# EVB-NORA-B2_SCHEM_0003_USBhub_FTDI.net
KiCad netlist of a schematic drawn in Altium Designer
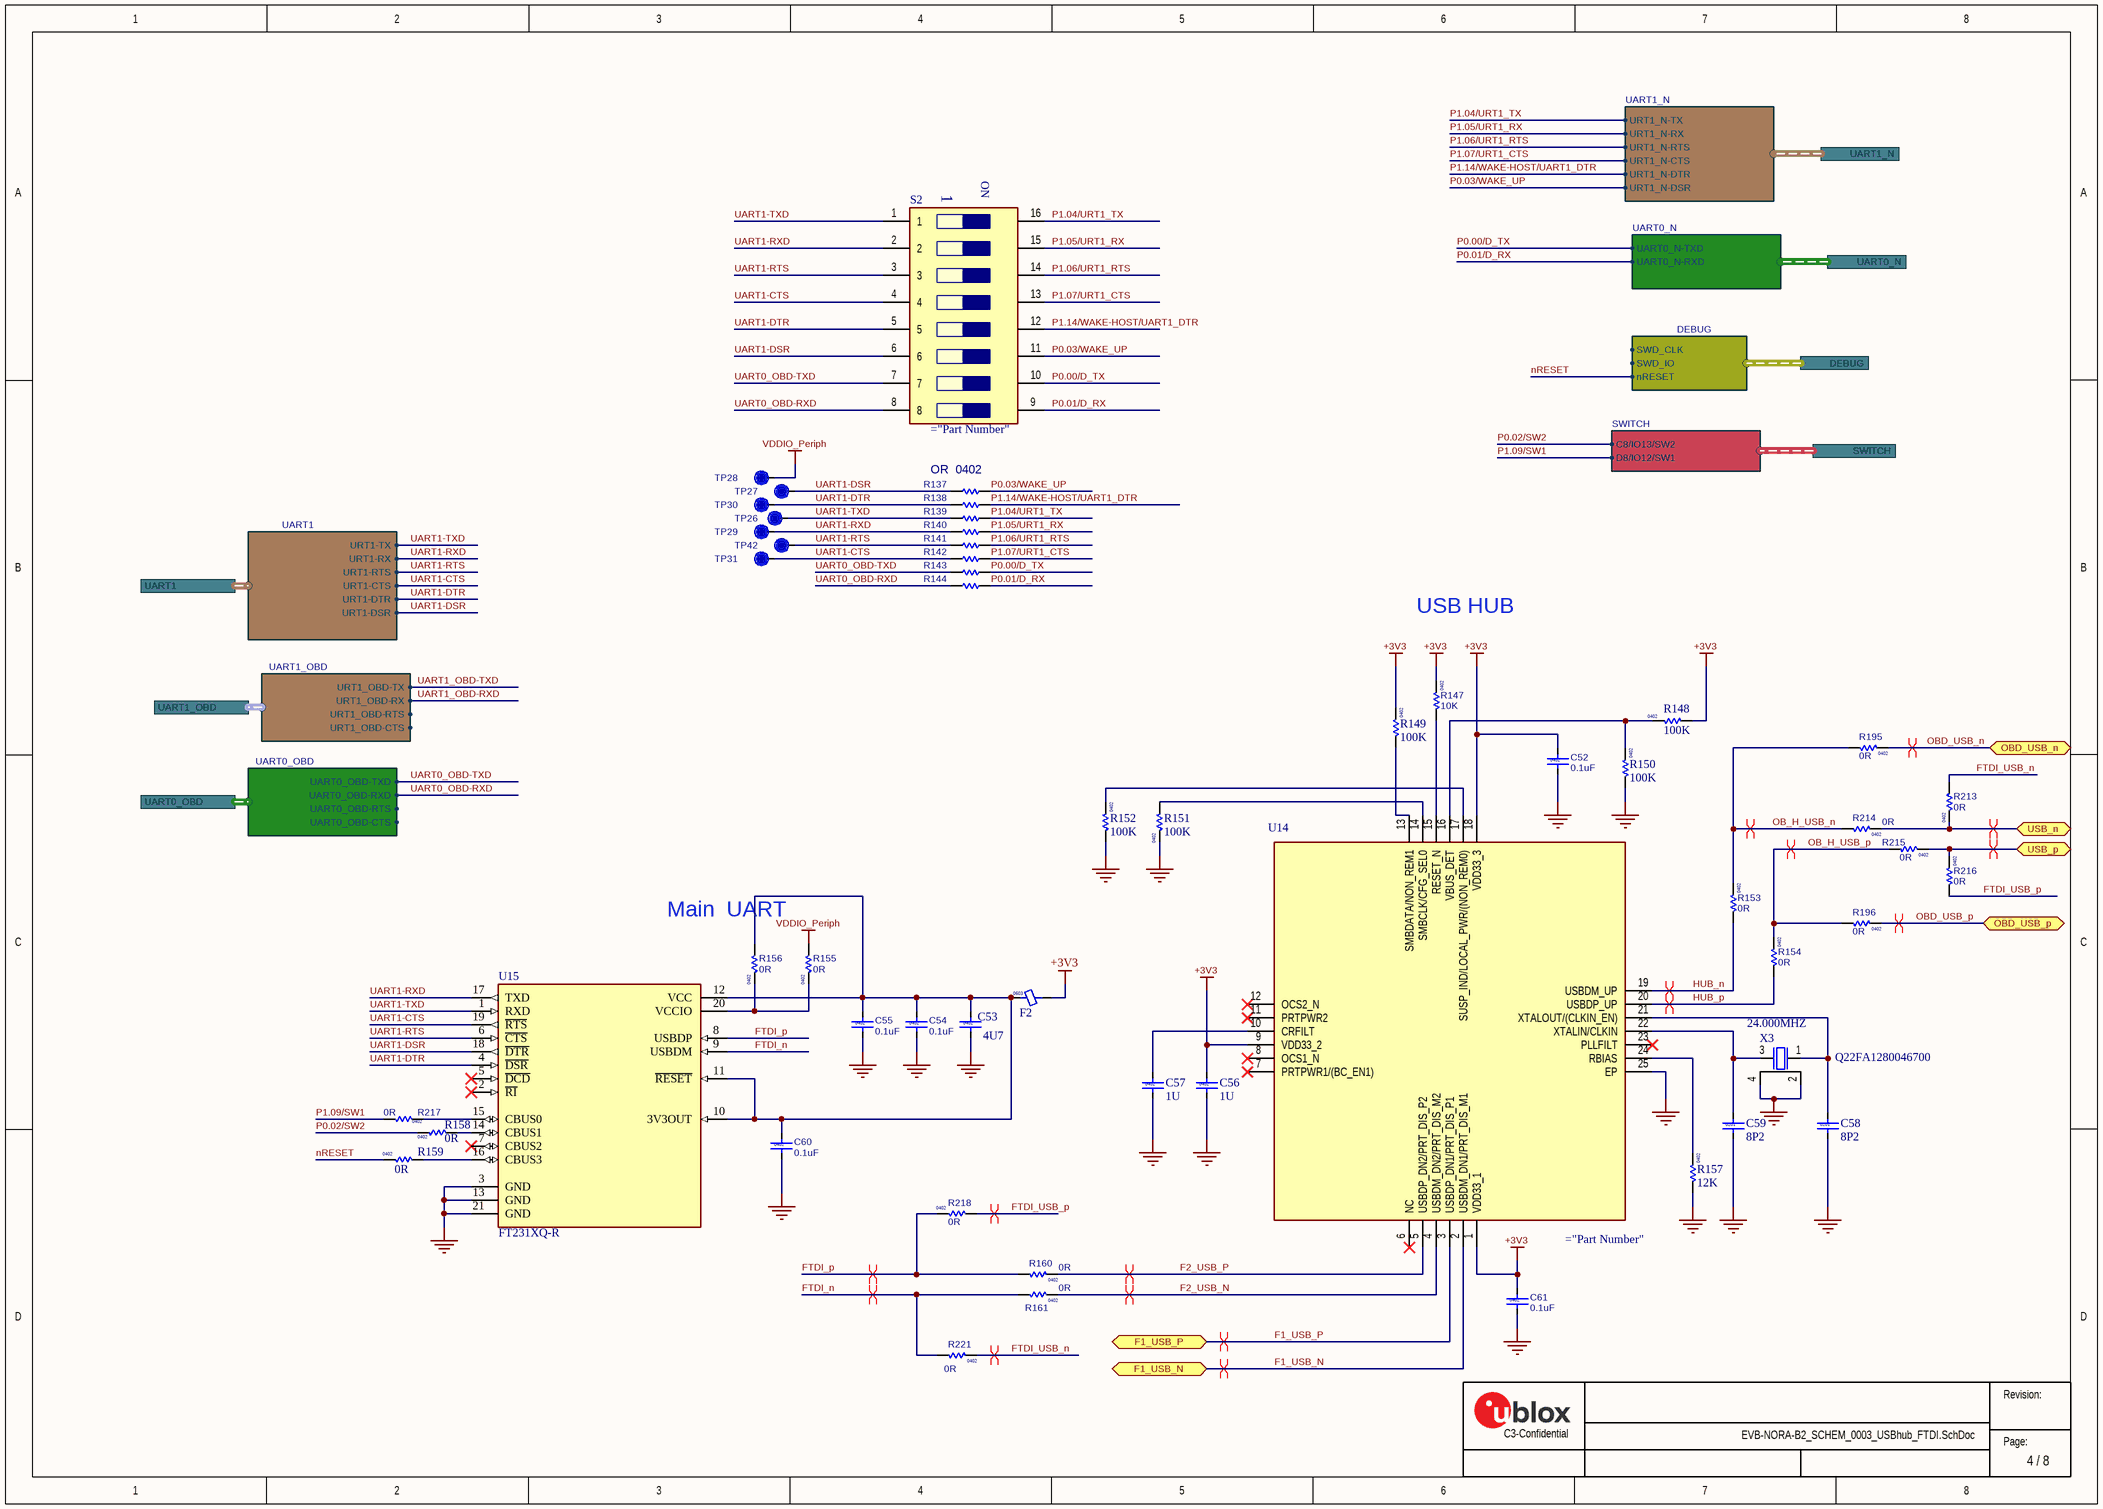
[diagram p0: EVB-NORA-B2_SCHEM_0003_USBhub_FTDI.SchDoc]

(export (version "E")
  (design (tool "Eeschema 10.0.6"))
  (components
    (comp (ref "C52")
      (value "0.1uF")
      (footprint "Cap 0402 HD")
      (description "Cap, Ceramic 0.1uF 10V 10% X5R 0402")
      (fields
        (field (name "SIZE") "0402")
        (field (name "PART NUMBER") "120-00016")
        (field (name "MANUFACTURER") "Murata Electronics North America")
      )
      (libsource (lib "Arena_Parts_DB_Lib") (part "Cap Chip"))
    )
    (comp (ref "C53")
      (value "4U7")
      (footprint "Cap 0402 HD")
      (description "CAP CER X5R 0402 4U7 20% 10V")
      (fields
        (field (name "SIZE") "0402")
        (field (name "PART NUMBER") "UBXH01-0000243")
        (field (name "TOLERANCE") "20%")
        (field (name "EDITOR") "martin.pilik")
        (field (name "RELEASED BY") "fabrice.bret-dibat")
      )
      (libsource (lib "UBX_Parts_DB_Lib") (part "Cap Chip"))
    )
    (comp (ref "C54")
      (value "0.1uF")
      (footprint "Cap 0402 HD")
      (description "Cap, Ceramic 0.1uF 10V 10% X5R 0402")
      (fields
        (field (name "SIZE") "0402")
        (field (name "PART NUMBER") "120-00016")
        (field (name "MANUFACTURER") "Murata Electronics North America")
      )
      (libsource (lib "Arena_Parts_DB_Lib") (part "Cap Chip"))
    )
    (comp (ref "C55")
      (value "0.1uF")
      (footprint "Cap 0402 HD")
      (description "Cap, Ceramic 0.1uF 10V 10% X5R 0402")
      (fields
        (field (name "SIZE") "0402")
        (field (name "PART NUMBER") "120-00016")
        (field (name "MANUFACTURER") "Murata Electronics North America")
      )
      (libsource (lib "Arena_Parts_DB_Lib") (part "Cap Chip"))
    )
    (comp (ref "C56")
      (value "1U")
      (footprint "Cap 0402 HD")
      (description "CAP CER X5R 0402 1U 10% 10V")
      (fields
        (field (name "SIZE") "0402")
        (field (name "PART NUMBER") "UBXH01-0000248")
        (field (name "TOLERANCE") "10%")
        (field (name "EDITOR") "michael.hein")
        (field (name "RELEASED BY") "igor.shevchenko")
      )
      (libsource (lib "UBX_Parts_DB_Lib") (part "Cap Chip"))
    )
    (comp (ref "C57")
      (value "1U")
      (footprint "Cap 0402 HD")
      (description "CAP CER X5R 0402 1U 10% 10V")
      (fields
        (field (name "SIZE") "0402")
        (field (name "PART NUMBER") "UBXH01-0000248")
        (field (name "TOLERANCE") "10%")
        (field (name "EDITOR") "michael.hein")
        (field (name "RELEASED BY") "igor.shevchenko")
      )
      (libsource (lib "UBX_Parts_DB_Lib") (part "Cap Chip"))
    )
    (comp (ref "C58")
      (value "8P2")
      (footprint "Cap 0201 HD")
      (description "CAP CER C0G 0201 8P2 +/-0.5P 25V")
      (fields
        (field (name "SIZE") "0201")
        (field (name "PART NUMBER") "UBXH01-0013002")
        (field (name "TOLERANCE") "+/-0.5P")
        (field (name "EDITOR") "roland.rust")
        (field (name "RELEASED BY") "roland.rust")
      )
      (libsource (lib "UBX_Parts_DB_Lib") (part "Cap Chip"))
    )
    (comp (ref "C59")
      (value "8P2")
      (footprint "Cap 0201 HD")
      (description "CAP CER C0G 0201 8P2 +/-0.5P 25V")
      (fields
        (field (name "SIZE") "0201")
        (field (name "PART NUMBER") "UBXH01-0013002")
        (field (name "TOLERANCE") "+/-0.5P")
        (field (name "EDITOR") "roland.rust")
        (field (name "RELEASED BY") "roland.rust")
      )
      (libsource (lib "UBX_Parts_DB_Lib") (part "Cap Chip"))
    )
    (comp (ref "C60")
      (value "0.1uF")
      (footprint "Cap 0402 HD")
      (description "Cap, Ceramic 0.1uF 10V 10% X5R 0402")
      (fields
        (field (name "SIZE") "0402")
        (field (name "PART NUMBER") "120-00016")
        (field (name "MANUFACTURER") "Murata Electronics North America")
      )
      (libsource (lib "Arena_Parts_DB_Lib") (part "Cap Chip"))
    )
    (comp (ref "C61")
      (value "0.1uF")
      (footprint "Cap 0402 HD")
      (description "Cap, Ceramic 0.1uF 10V 10% X5R 0402")
      (fields
        (field (name "SIZE") "0402")
        (field (name "PART NUMBER") "120-00016")
        (field (name "MANUFACTURER") "Murata Electronics North America")
      )
      (libsource (lib "Arena_Parts_DB_Lib") (part "Cap Chip"))
    )
    (comp (ref "F2")
      (value "UBXH08-0000001")
      (footprint "IND_0603_1750Lx950Wx1050H_600x800Pad_800G_FLX")
      (description "FERRITE BEAD 0603 600 OHM AT 100MHZ 600OHM 500mA")
      (fields
        (field (name "SIZE") "0603")
        (field (name "MANUFACTURER") "TDK Corporation")
        (field (name "EDITOR") "daniel.hurni")
        (field (name "RELEASED BY") "martin.frauchiger")
      )
      (libsource (lib "UBX_Parts_DB_Lib") (part "FB sm"))
    )
    (comp (ref "R137")
      (value "UBXH18-0003002")
      (footprint "RES 0402 HD")
      (description "RES THICK FILM CHIP 0402 0R 0 100mW")
      (fields
        (field (name "TOLERANCE") "0")
        (field (name "MANUFACTURER") "KOA")
        (field (name "EDITOR") "charlotte.biber")
        (field (name "RELEASED BY") "peter.mueller")
      )
      (libsource (lib "UBX_Parts_DB_Lib") (part "Res sm"))
    )
    (comp (ref "R138")
      (value "UBXH18-0003002")
      (footprint "RES 0402 HD")
      (description "RES THICK FILM CHIP 0402 0R 0 100mW")
      (fields
        (field (name "TOLERANCE") "0")
        (field (name "MANUFACTURER") "KOA")
        (field (name "EDITOR") "charlotte.biber")
        (field (name "RELEASED BY") "peter.mueller")
      )
      (libsource (lib "UBX_Parts_DB_Lib") (part "Res sm"))
    )
    (comp (ref "R139")
      (value "UBXH18-0003002")
      (footprint "RES 0402 HD")
      (description "RES THICK FILM CHIP 0402 0R 0 100mW")
      (fields
        (field (name "TOLERANCE") "0")
        (field (name "MANUFACTURER") "KOA")
        (field (name "EDITOR") "charlotte.biber")
        (field (name "RELEASED BY") "peter.mueller")
      )
      (libsource (lib "UBX_Parts_DB_Lib") (part "Res sm"))
    )
    (comp (ref "R140")
      (value "UBXH18-0003002")
      (footprint "RES 0402 HD")
      (description "RES THICK FILM CHIP 0402 0R 0 100mW")
      (fields
        (field (name "TOLERANCE") "0")
        (field (name "MANUFACTURER") "KOA")
        (field (name "EDITOR") "charlotte.biber")
        (field (name "RELEASED BY") "peter.mueller")
      )
      (libsource (lib "UBX_Parts_DB_Lib") (part "Res sm"))
    )
    (comp (ref "R141")
      (value "UBXH18-0003002")
      (footprint "RES 0402 HD")
      (description "RES THICK FILM CHIP 0402 0R 0 100mW")
      (fields
        (field (name "TOLERANCE") "0")
        (field (name "MANUFACTURER") "KOA")
        (field (name "EDITOR") "charlotte.biber")
        (field (name "RELEASED BY") "peter.mueller")
      )
      (libsource (lib "UBX_Parts_DB_Lib") (part "Res sm"))
    )
    (comp (ref "R142")
      (value "UBXH18-0003002")
      (footprint "RES 0402 HD")
      (description "RES THICK FILM CHIP 0402 0R 0 100mW")
      (fields
        (field (name "TOLERANCE") "0")
        (field (name "MANUFACTURER") "KOA")
        (field (name "EDITOR") "charlotte.biber")
        (field (name "RELEASED BY") "peter.mueller")
      )
      (libsource (lib "UBX_Parts_DB_Lib") (part "Res sm"))
    )
    (comp (ref "R143")
      (value "UBXH18-0003002")
      (footprint "RES 0402 HD")
      (description "RES THICK FILM CHIP 0402 0R 0 100mW")
      (fields
        (field (name "TOLERANCE") "0")
        (field (name "MANUFACTURER") "KOA")
        (field (name "EDITOR") "charlotte.biber")
        (field (name "RELEASED BY") "peter.mueller")
      )
      (libsource (lib "UBX_Parts_DB_Lib") (part "Res sm"))
    )
    (comp (ref "R144")
      (value "UBXH18-0003002")
      (footprint "RES 0402 HD")
      (description "RES THICK FILM CHIP 0402 0R 0 100mW")
      (fields
        (field (name "TOLERANCE") "0")
        (field (name "MANUFACTURER") "KOA")
        (field (name "EDITOR") "charlotte.biber")
        (field (name "RELEASED BY") "peter.mueller")
      )
      (libsource (lib "UBX_Parts_DB_Lib") (part "Res sm"))
    )
    (comp (ref "R147")
      (value "10K")
      (footprint "RES 0402 HD")
      (description "RES THICK FILM CHIP 0402 10K 1% 63mW")
      (fields
        (field (name "SIZE") "0402")
        (field (name "PART NUMBER") "UBXH18-0000065")
        (field (name "TOLERANCE") "1%")
        (field (name "EDITOR") "erian.bezhani")
        (field (name "RELEASED BY") "massimo.vlacci")
      )
      (libsource (lib "UBX_Parts_DB_Lib") (part "Res sm"))
    )
    (comp (ref "R148")
      (value "100K")
      (footprint "RES 0402 HD")
      (description "RES THICK FILM CHIP 0402 100K 1% 63mW")
      (fields
        (field (name "SIZE") "0402")
        (field (name "PART NUMBER") "UBXH18-0000005")
        (field (name "TOLERANCE") "1%")
        (field (name "EDITOR") "dario.antonaz")
        (field (name "RELEASED BY") "sandro.sestan")
      )
      (libsource (lib "UBX_Parts_DB_Lib") (part "Res sm"))
    )
    (comp (ref "R149")
      (value "100K")
      (footprint "RES 0402 HD")
      (description "RES THICK FILM CHIP 0402 100K 1% 63mW")
      (fields
        (field (name "SIZE") "0402")
        (field (name "PART NUMBER") "UBXH18-0000005")
        (field (name "TOLERANCE") "1%")
        (field (name "EDITOR") "dario.antonaz")
        (field (name "RELEASED BY") "sandro.sestan")
      )
      (libsource (lib "UBX_Parts_DB_Lib") (part "Res sm"))
    )
    (comp (ref "R150")
      (value "100K")
      (footprint "RES 0402 HD")
      (description "RES THICK FILM CHIP 0402 100K 1% 63mW")
      (fields
        (field (name "SIZE") "0402")
        (field (name "PART NUMBER") "UBXH18-0000005")
        (field (name "TOLERANCE") "1%")
        (field (name "EDITOR") "dario.antonaz")
        (field (name "RELEASED BY") "sandro.sestan")
      )
      (libsource (lib "UBX_Parts_DB_Lib") (part "Res sm"))
    )
    (comp (ref "R151")
      (value "100K")
      (footprint "RES 0402 HD")
      (description "RES THICK FILM CHIP 0402 100K 1% 63mW")
      (fields
        (field (name "SIZE") "0402")
        (field (name "PART NUMBER") "UBXH18-0000005")
        (field (name "TOLERANCE") "1%")
        (field (name "EDITOR") "dario.antonaz")
        (field (name "RELEASED BY") "sandro.sestan")
      )
      (libsource (lib "UBX_Parts_DB_Lib") (part "Res sm"))
    )
    (comp (ref "R152")
      (value "100K")
      (footprint "RES 0402 HD")
      (description "RES THICK FILM CHIP 0402 100K 1% 63mW")
      (fields
        (field (name "SIZE") "0402")
        (field (name "PART NUMBER") "UBXH18-0000005")
        (field (name "TOLERANCE") "1%")
        (field (name "EDITOR") "dario.antonaz")
        (field (name "RELEASED BY") "sandro.sestan")
      )
      (libsource (lib "UBX_Parts_DB_Lib") (part "Res sm"))
    )
    (comp (ref "R153")
      (value "0R")
      (footprint "RES 0402 HD")
      (description "RES THICK FILM CHIP 0402 0R 0 100mW")
      (fields
        (field (name "SIZE") "0402")
        (field (name "PART NUMBER") "UBXH18-0003002")
        (field (name "TOLERANCE") "0")
        (field (name "EDITOR") "charlotte.biber")
        (field (name "RELEASED BY") "peter.mueller")
      )
      (libsource (lib "UBX_Parts_DB_Lib") (part "Res sm"))
    )
    (comp (ref "R154")
      (value "0R")
      (footprint "RES 0402 HD")
      (description "RES THICK FILM CHIP 0402 0R 0 100mW")
      (fields
        (field (name "SIZE") "0402")
        (field (name "PART NUMBER") "UBXH18-0003002")
        (field (name "TOLERANCE") "0")
        (field (name "EDITOR") "charlotte.biber")
        (field (name "RELEASED BY") "peter.mueller")
      )
      (libsource (lib "UBX_Parts_DB_Lib") (part "Res sm"))
    )
    (comp (ref "R155")
      (value "0R")
      (footprint "RES 0402 HD")
      (description "RES THICK FILM CHIP 0402 0R 0 100mW")
      (fields
        (field (name "SIZE") "0402")
        (field (name "PART NUMBER") "UBXH18-0003002")
        (field (name "TOLERANCE") "0")
        (field (name "EDITOR") "charlotte.biber")
        (field (name "RELEASED BY") "peter.mueller")
      )
      (libsource (lib "UBX_Parts_DB_Lib") (part "Res sm"))
    )
    (comp (ref "R156")
      (value "0R")
      (footprint "RES 0402 HD")
      (description "RES THICK FILM CHIP 0402 0R 0 100mW")
      (fields
        (field (name "SIZE") "0402")
        (field (name "PART NUMBER") "UBXH18-0003002")
        (field (name "TOLERANCE") "0")
        (field (name "EDITOR") "charlotte.biber")
        (field (name "RELEASED BY") "peter.mueller")
      )
      (libsource (lib "UBX_Parts_DB_Lib") (part "Res sm"))
    )
    (comp (ref "R157")
      (value "12K")
      (footprint "RES_0402_1100Lx600Wx400H_500x600Pad_400G_FLX")
      (description "RES THICK FILM CHIP 0402 12K 1% 62.5mW")
      (fields
        (field (name "SIZE") "0402")
        (field (name "PART NUMBER") "UBXH18-0000133")
        (field (name "TOLERANCE") "1%")
        (field (name "EDITOR") "pierpaolo.arban")
        (field (name "RELEASED BY") "dario.antonaz")
      )
      (libsource (lib "UBX_Parts_DB_Lib") (part "Res sm"))
    )
    (comp (ref "R158")
      (value "0R")
      (footprint "RES_0402_1100Lx600Wx400H_500x600Pad_400G_FLX")
      (description "RES THICK FILM CHIP 0402 0R 0 100mW")
      (fields
        (field (name "SIZE") "0402")
        (field (name "PART NUMBER") "UBXH18-0003002")
        (field (name "TOLERANCE") "0")
        (field (name "EDITOR") "charlotte.biber")
        (field (name "RELEASED BY") "peter.mueller")
      )
      (libsource (lib "UBX_Parts_DB_Lib") (part "Res sm"))
    )
    (comp (ref "R159")
      (value "0R")
      (footprint "RES_0402_1100Lx600Wx400H_500x600Pad_400G_FLX")
      (description "RES THICK FILM CHIP 0402 0R 0 100mW")
      (fields
        (field (name "SIZE") "0402")
        (field (name "PART NUMBER") "UBXH18-0003002")
        (field (name "TOLERANCE") "0")
        (field (name "EDITOR") "charlotte.biber")
        (field (name "RELEASED BY") "peter.mueller")
      )
      (libsource (lib "UBX_Parts_DB_Lib") (part "Res sm"))
    )
    (comp (ref "R160")
      (value "0R")
      (footprint "RES 0402 HD")
      (description "RES THICK FILM CHIP 0402 0R 0 100mW")
      (fields
        (field (name "SIZE") "0402")
        (field (name "PART NUMBER") "UBXH18-0003002")
        (field (name "TOLERANCE") "0")
        (field (name "EDITOR") "charlotte.biber")
        (field (name "RELEASED BY") "peter.mueller")
      )
      (libsource (lib "UBX_Parts_DB_Lib") (part "Res sm"))
    )
    (comp (ref "R161")
      (value "0R")
      (footprint "RES 0402 HD")
      (description "RES THICK FILM CHIP 0402 0R 0 100mW")
      (fields
        (field (name "SIZE") "0402")
        (field (name "PART NUMBER") "UBXH18-0003002")
        (field (name "TOLERANCE") "0")
        (field (name "EDITOR") "charlotte.biber")
        (field (name "RELEASED BY") "peter.mueller")
      )
      (libsource (lib "UBX_Parts_DB_Lib") (part "Res sm"))
    )
    (comp (ref "R195")
      (value "0R")
      (footprint "RES 0402 HD")
      (description "RES THICK FILM CHIP 0402 0R 0 100mW")
      (fields
        (field (name "SIZE") "0402")
        (field (name "PART NUMBER") "UBXH18-0003002")
        (field (name "TOLERANCE") "0")
        (field (name "EDITOR") "charlotte.biber")
        (field (name "RELEASED BY") "peter.mueller")
      )
      (libsource (lib "UBX_Parts_DB_Lib") (part "Res sm"))
    )
    (comp (ref "R196")
      (value "0R")
      (footprint "RES 0402 HD")
      (description "RES THICK FILM CHIP 0402 0R 0 100mW")
      (fields
        (field (name "SIZE") "0402")
        (field (name "PART NUMBER") "UBXH18-0003002")
        (field (name "TOLERANCE") "0")
        (field (name "EDITOR") "charlotte.biber")
        (field (name "RELEASED BY") "peter.mueller")
      )
      (libsource (lib "UBX_Parts_DB_Lib") (part "Res sm"))
    )
    (comp (ref "R213")
      (value "0R")
      (footprint "RES 0402 HD")
      (description "RES THICK FILM CHIP 0402 0R 0 100mW")
      (fields
        (field (name "SIZE") "0402")
        (field (name "PART NUMBER") "UBXH18-0003002")
        (field (name "TOLERANCE") "0")
        (field (name "EDITOR") "charlotte.biber")
        (field (name "RELEASED BY") "peter.mueller")
      )
      (libsource (lib "UBX_Parts_DB_Lib") (part "Res sm"))
    )
    (comp (ref "R214")
      (value "0R")
      (footprint "RES 0402 HD")
      (description "RES THICK FILM CHIP 0402 0R 0 100mW")
      (fields
        (field (name "SIZE") "0402")
        (field (name "PART NUMBER") "UBXH18-0003002")
        (field (name "TOLERANCE") "0")
        (field (name "EDITOR") "charlotte.biber")
        (field (name "RELEASED BY") "peter.mueller")
      )
      (libsource (lib "UBX_Parts_DB_Lib") (part "Res sm"))
    )
    (comp (ref "R215")
      (value "0R")
      (footprint "RES 0402 HD")
      (description "RES THICK FILM CHIP 0402 0R 0 100mW")
      (fields
        (field (name "SIZE") "0402")
        (field (name "PART NUMBER") "UBXH18-0003002")
        (field (name "TOLERANCE") "0")
        (field (name "EDITOR") "charlotte.biber")
        (field (name "RELEASED BY") "peter.mueller")
      )
      (libsource (lib "UBX_Parts_DB_Lib") (part "Res sm"))
    )
    (comp (ref "R216")
      (value "0R")
      (footprint "RES 0402 HD")
      (description "RES THICK FILM CHIP 0402 0R 0 100mW")
      (fields
        (field (name "SIZE") "0402")
        (field (name "PART NUMBER") "UBXH18-0003002")
        (field (name "TOLERANCE") "0")
        (field (name "EDITOR") "charlotte.biber")
        (field (name "RELEASED BY") "peter.mueller")
      )
      (libsource (lib "UBX_Parts_DB_Lib") (part "Res sm"))
    )
    (comp (ref "R217")
      (value "0R")
      (footprint "RES 0402 HD")
      (description "RES THICK FILM CHIP 0402 0R 0 100mW")
      (fields
        (field (name "SIZE") "0402")
        (field (name "PART NUMBER") "UBXH18-0003002")
        (field (name "TOLERANCE") "0")
        (field (name "EDITOR") "charlotte.biber")
        (field (name "RELEASED BY") "peter.mueller")
      )
      (libsource (lib "UBX_Parts_DB_Lib") (part "Res sm"))
    )
    (comp (ref "R218")
      (value "0R")
      (footprint "RES 0402 HD")
      (description "RES THICK FILM CHIP 0402 0R 0 100mW")
      (fields
        (field (name "SIZE") "0402")
        (field (name "PART NUMBER") "UBXH18-0003002")
        (field (name "TOLERANCE") "0")
        (field (name "EDITOR") "charlotte.biber")
        (field (name "RELEASED BY") "peter.mueller")
      )
      (libsource (lib "UBX_Parts_DB_Lib") (part "Res sm"))
    )
    (comp (ref "R221")
      (value "0R")
      (footprint "RES 0402 HD")
      (description "RES THICK FILM CHIP 0402 0R 0 100mW")
      (fields
        (field (name "SIZE") "0402")
        (field (name "PART NUMBER") "UBXH18-0003002")
        (field (name "TOLERANCE") "0")
        (field (name "EDITOR") "charlotte.biber")
        (field (name "RELEASED BY") "peter.mueller")
      )
      (libsource (lib "UBX_Parts_DB_Lib") (part "Res sm"))
    )
    (comp (ref "S2")
      (value "~")
      (footprint "2188LPSTJ")
      (description "Switch")
      (fields
        (field (name "MANUFACTURER_PART_NUMBER") "218-8LPSTJ")
        (field (name "MOUSER PART NUMBER") "774-2188LPSTJ")
      )
      (libsource (lib "SamacSys") (part "218-8LPSTJ"))
    )
    (comp (ref "TP26")
      (value "TP10R")
      (footprint "TP10R")
      (description "Testpoint, Round 1.0mm Dia")
      (fields (field (name "ADDED BY") "Jeremy D") (field (name "CHECKED BY") "Paul B"))
      (libsource (lib "LEGACY_Rigado_AltiumLib") (part "TP_R"))
    )
    (comp (ref "TP27")
      (value "TP10R")
      (footprint "TP10R")
      (description "Testpoint, Round 1.0mm Dia")
      (fields (field (name "ADDED BY") "Jeremy D") (field (name "CHECKED BY") "Paul B"))
      (libsource (lib "LEGACY_Rigado_AltiumLib") (part "TP_R"))
    )
    (comp (ref "TP28")
      (value "TP10R")
      (footprint "TP10R")
      (description "Testpoint, Round 1.0mm Dia")
      (fields (field (name "ADDED BY") "Jeremy D") (field (name "CHECKED BY") "Paul B"))
      (libsource (lib "LEGACY_Rigado_AltiumLib") (part "TP_R"))
    )
    (comp (ref "TP29")
      (value "TP10R")
      (footprint "TP10R")
      (description "Testpoint, Round 1.0mm Dia")
      (fields (field (name "ADDED BY") "Jeremy D") (field (name "CHECKED BY") "Paul B"))
      (libsource (lib "LEGACY_Rigado_AltiumLib") (part "TP_R"))
    )
    (comp (ref "TP30")
      (value "TP10R")
      (footprint "TP10R")
      (description "Testpoint, Round 1.0mm Dia")
      (fields (field (name "ADDED BY") "Jeremy D") (field (name "CHECKED BY") "Paul B"))
      (libsource (lib "LEGACY_Rigado_AltiumLib") (part "TP_R"))
    )
    (comp (ref "TP31")
      (value "TP10R")
      (footprint "TP10R")
      (description "Testpoint, Round 1.0mm Dia")
      (fields (field (name "ADDED BY") "Jeremy D") (field (name "CHECKED BY") "Paul B"))
      (libsource (lib "LEGACY_Rigado_AltiumLib") (part "TP_R"))
    )
    (comp (ref "TP42")
      (value "TP10R")
      (footprint "TP10R")
      (description "Testpoint, Round 1.0mm Dia")
      (fields (field (name "ADDED BY") "Jeremy D") (field (name "CHECKED BY") "Paul B"))
      (libsource (lib "LEGACY_Rigado_AltiumLib") (part "TP_R"))
    )
    (comp (ref "U14")
      (value "~")
      (footprint "SamacSys:QFN50P400X400X100-25N-D")
      (description "Integrated Circuit")
      (fields
        (field (name "MANUFACTURER_PART_NUMBER") "USB2422-I/MJ")
        (field (name "MOUSER PART NUMBER") "579-USB2422-I/MJ")
      )
      (libsource (lib "*") (part "USB2422-I_MJ"))
    )
    (comp (ref "U15")
      (value "FT231XQ-R")
      (footprint "QFN_5x5_FT231XQ")
      (description "FTDI USB TO SERIAL FULL UART INTERFACE QFN20")
      (fields
        (field (name "PART NUMBER") "UBXH10-0000054")
        (field (name "MANUFACTURER") "FTDI Future Technology Devices International")
        (field (name "EDITOR") "adam.johansson")
      )
      (libsource (lib "UBX_Parts_DB_Lib") (part "FT231XQ-R"))
    )
    (comp (ref "X3")
      (value "24.000MHZ")
      (footprint "XTAL_2016_HD")
      (description "CRYSTAL CL=8PF EPSON 2.0X1.6MM 24.000MHZ 30PPM")
      (fields
        (field (name "PART NUMBER") "UBXH21-0000066")
        (field (name "TOLERANCE") "30PPM")
        (field (name "MANUFACTURER P/N") "Q22FA1280046700")
        (field (name "EDITOR") "adam.johansson")
        (field (name "RELEASED BY") "olof.viklund")
      )
      (libsource (lib "UBX_Parts_DB_Lib") (part "XTAL_4Pin"))
    )
  )
  (nets
    (net (code "8") (name "+3V3") (class "Default")
      (node (ref "C52") (pin "1") (pinfunction "1_1") (pintype "passive"))
      (node (ref "C56") (pin "1") (pinfunction "1_1") (pintype "passive"))
      (node (ref "C61") (pin "1") (pinfunction "1_1") (pintype "passive"))
      (node (ref "F2") (pin "1") (pinfunction "1_1") (pintype "passive"))
      (node (ref "R147") (pin "2") (pinfunction "2_2") (pintype "passive"))
      (node (ref "R148") (pin "2") (pinfunction "2_2") (pintype "passive"))
      (node (ref "R149") (pin "2") (pinfunction "2_2") (pintype "passive"))
      (node (ref "U14") (pin "1") (pinfunction "VDD33_1_1") (pintype "passive"))
      (node (ref "U14") (pin "18") (pinfunction "VDD33_3_18") (pintype "passive"))
      (node (ref "U14") (pin "9") (pinfunction "VDD33_2_9") (pintype "passive"))
    )
    (net (code "9") (name "/F1_USB_N") (class "Default")
      (node (ref "U14") (pin "2") (pinfunction "USBDM_DN1/PRT_DIS_M1_2") (pintype "passive"))
    )
    (net (code "10") (name "/F1_USB_P") (class "Default")
      (node (ref "U14") (pin "3") (pinfunction "USBDP_DN1/PRT_DIS_P1_3") (pintype "passive"))
    )
    (net (code "11") (name "/F2_USB_N") (class "Default")
      (node (ref "R161") (pin "2") (pinfunction "2_2") (pintype "passive"))
      (node (ref "U14") (pin "4") (pinfunction "USBDM_DN2/PRT_DIS_M2_4") (pintype "passive"))
    )
    (net (code "12") (name "/F2_USB_P") (class "Default")
      (node (ref "R160") (pin "2") (pinfunction "2_2") (pintype "passive"))
      (node (ref "U14") (pin "5") (pinfunction "USBDP_DN2/PRT_DIS_P2_5") (pintype "passive"))
    )
    (net (code "13") (name "/FTDI_USB_n") (class "Default")
      (node (ref "R213") (pin "1") (pinfunction "1_1") (pintype "passive"))
      (node (ref "R221") (pin "2") (pinfunction "2_2") (pintype "passive"))
    )
    (net (code "14") (name "/FTDI_USB_p") (class "Default")
      (node (ref "R216") (pin "1") (pinfunction "1_1") (pintype "passive"))
      (node (ref "R218") (pin "1") (pinfunction "1_1") (pintype "passive"))
    )
    (net (code "15") (name "/FTDI_n") (class "Default")
      (node (ref "R161") (pin "1") (pinfunction "1_1") (pintype "passive"))
      (node (ref "R221") (pin "1") (pinfunction "1_1") (pintype "passive"))
      (node (ref "U15") (pin "9") (pinfunction "USBDM_9") (pintype "input"))
    )
    (net (code "16") (name "/FTDI_p") (class "Default")
      (node (ref "R160") (pin "1") (pinfunction "1_1") (pintype "passive"))
      (node (ref "R218") (pin "2") (pinfunction "2_2") (pintype "passive"))
      (node (ref "U15") (pin "8") (pinfunction "USBDP_8") (pintype "input"))
    )
    (net (code "17") (name "/HUB_n") (class "Default")
      (node (ref "R153") (pin "1") (pinfunction "1_1") (pintype "passive"))
      (node (ref "U14") (pin "19") (pinfunction "USBDM_UP_19") (pintype "passive"))
    )
    (net (code "18") (name "/HUB_p") (class "Default")
      (node (ref "R154") (pin "1") (pinfunction "1_1") (pintype "passive"))
      (node (ref "U14") (pin "20") (pinfunction "USBDP_UP_20") (pintype "passive"))
    )
    (net (code "19") (name "/OBD_USB_n") (class "Default")
      (node (ref "R195") (pin "2") (pinfunction "2_2") (pintype "passive"))
    )
    (net (code "20") (name "/OBD_USB_p") (class "Default")
      (node (ref "R196") (pin "2") (pinfunction "2_2") (pintype "passive"))
    )
    (net (code "21") (name "/OB_H_USB_n") (class "Default")
      (node (ref "R153") (pin "2") (pinfunction "2_2") (pintype "passive"))
      (node (ref "R195") (pin "1") (pinfunction "1_1") (pintype "passive"))
      (node (ref "R214") (pin "1") (pinfunction "1_1") (pintype "passive"))
    )
    (net (code "22") (name "/OB_H_USB_p") (class "Default")
      (node (ref "R154") (pin "2") (pinfunction "2_2") (pintype "passive"))
      (node (ref "R196") (pin "1") (pinfunction "1_1") (pintype "passive"))
      (node (ref "R215") (pin "1") (pinfunction "1_1") (pintype "passive"))
    )
    (net (code "23") (name "/P0.00{slash}D_TX") (class "Default")
      (node (ref "R143") (pin "2") (pinfunction "2_2") (pintype "passive"))
      (node (ref "S2") (pin "10") (pintype "passive"))
    )
    (net (code "24") (name "/P0.01{slash}D_RX") (class "Default")
      (node (ref "R144") (pin "2") (pinfunction "2_2") (pintype "passive"))
      (node (ref "S2") (pin "9") (pintype "passive"))
    )
    (net (code "25") (name "/P0.02{slash}SW2") (class "Default")
      (node (ref "R158") (pin "2") (pinfunction "2_2") (pintype "passive"))
    )
    (net (code "26") (name "/P0.03{slash}WAKE_UP") (class "Default")
      (node (ref "R137") (pin "2") (pinfunction "2_2") (pintype "passive"))
      (node (ref "S2") (pin "11") (pintype "passive"))
    )
    (net (code "27") (name "/P1.04{slash}URT1_TX") (class "Default")
      (node (ref "R139") (pin "2") (pinfunction "2_2") (pintype "passive"))
      (node (ref "S2") (pin "16") (pintype "passive"))
    )
    (net (code "28") (name "/P1.05{slash}URT1_RX") (class "Default")
      (node (ref "R140") (pin "2") (pinfunction "2_2") (pintype "passive"))
      (node (ref "S2") (pin "15") (pintype "passive"))
    )
    (net (code "29") (name "/P1.06{slash}URT1_RTS") (class "Default")
      (node (ref "R141") (pin "2") (pinfunction "2_2") (pintype "passive"))
      (node (ref "S2") (pin "14") (pintype "passive"))
    )
    (net (code "30") (name "/P1.07{slash}URT1_CTS") (class "Default")
      (node (ref "R142") (pin "2") (pinfunction "2_2") (pintype "passive"))
      (node (ref "S2") (pin "13") (pintype "passive"))
    )
    (net (code "31") (name "/P1.09{slash}SW1") (class "Default")
      (node (ref "R217") (pin "1") (pinfunction "1_1") (pintype "passive"))
    )
    (net (code "32") (name "/P1.14{slash}WAKE-HOST{slash}UART1_DTR") (class "Default")
      (node (ref "R138") (pin "2") (pinfunction "2_2") (pintype "passive"))
      (node (ref "S2") (pin "12") (pintype "passive"))
    )
    (net (code "33") (name "/UART0_OBD-RXD") (class "Default")
      (node (ref "R144") (pin "1") (pinfunction "1_1") (pintype "passive"))
      (node (ref "S2") (pin "8") (pinfunction "8_8") (pintype "passive"))
    )
    (net (code "34") (name "/UART0_OBD-TXD") (class "Default")
      (node (ref "R143") (pin "1") (pinfunction "1_1") (pintype "passive"))
      (node (ref "S2") (pin "7") (pinfunction "7_7") (pintype "passive"))
    )
    (net (code "35") (name "/UART1-CTS") (class "Default")
      (node (ref "R142") (pin "1") (pinfunction "1_1") (pintype "passive"))
      (node (ref "S2") (pin "4") (pinfunction "4_4") (pintype "passive"))
      (node (ref "TP31") (pin "1") (pintype "passive"))
      (node (ref "U15") (pin "19") (pinfunction "~{RTS}_19") (pintype "output"))
    )
    (net (code "36") (name "/UART1-DSR") (class "Default")
      (node (ref "R137") (pin "1") (pinfunction "1_1") (pintype "passive"))
      (node (ref "S2") (pin "6") (pinfunction "6_6") (pintype "passive"))
      (node (ref "TP27") (pin "1") (pintype "passive"))
      (node (ref "U15") (pin "18") (pinfunction "~{DTR}_18") (pintype "output"))
    )
    (net (code "37") (name "/UART1-DTR") (class "Default")
      (node (ref "R138") (pin "1") (pinfunction "1_1") (pintype "passive"))
      (node (ref "S2") (pin "5") (pinfunction "5_5") (pintype "passive"))
      (node (ref "TP30") (pin "1") (pintype "passive"))
      (node (ref "U15") (pin "4") (pinfunction "~{DSR}_4") (pintype "input"))
    )
    (net (code "38") (name "/UART1-RTS") (class "Default")
      (node (ref "R141") (pin "1") (pinfunction "1_1") (pintype "passive"))
      (node (ref "S2") (pin "3") (pinfunction "3_3") (pintype "passive"))
      (node (ref "TP42") (pin "1") (pintype "passive"))
      (node (ref "U15") (pin "6") (pinfunction "~{CTS}_6") (pintype "input"))
    )
    (net (code "39") (name "/UART1-RXD") (class "Default")
      (node (ref "R140") (pin "1") (pinfunction "1_1") (pintype "passive"))
      (node (ref "S2") (pin "2") (pinfunction "2_2") (pintype "passive"))
      (node (ref "TP29") (pin "1") (pintype "passive"))
      (node (ref "U15") (pin "17") (pinfunction "TXD_17") (pintype "output"))
    )
    (net (code "40") (name "/UART1-TXD") (class "Default")
      (node (ref "R139") (pin "1") (pinfunction "1_1") (pintype "passive"))
      (node (ref "S2") (pin "1") (pinfunction "1_1") (pintype "passive"))
      (node (ref "TP26") (pin "1") (pintype "passive"))
      (node (ref "U15") (pin "1") (pinfunction "RXD_1") (pintype "input"))
    )
    (net (code "43") (name "/USB_n") (class "Default")
      (node (ref "R213") (pin "2") (pinfunction "2_2") (pintype "passive"))
      (node (ref "R214") (pin "2") (pinfunction "2_2") (pintype "passive"))
    )
    (net (code "44") (name "/USB_p") (class "Default")
      (node (ref "R215") (pin "2") (pinfunction "2_2") (pintype "passive"))
      (node (ref "R216") (pin "2") (pinfunction "2_2") (pintype "passive"))
    )
    (net (code "45") (name "/nRESET") (class "Default")
      (node (ref "R159") (pin "2") (pinfunction "2_2") (pintype "passive"))
    )
    (net (code "53") (name "GND") (class "Default")
      (node (ref "C52") (pin "2") (pinfunction "2_2") (pintype "passive"))
      (node (ref "C53") (pin "2") (pinfunction "2_2") (pintype "passive"))
      (node (ref "C54") (pin "2") (pinfunction "2_2") (pintype "passive"))
      (node (ref "C55") (pin "2") (pinfunction "2_2") (pintype "passive"))
      (node (ref "C56") (pin "2") (pinfunction "2_2") (pintype "passive"))
      (node (ref "C57") (pin "2") (pinfunction "2_2") (pintype "passive"))
      (node (ref "C58") (pin "2") (pinfunction "2_2") (pintype "passive"))
      (node (ref "C59") (pin "2") (pinfunction "2_2") (pintype "passive"))
      (node (ref "C60") (pin "2") (pinfunction "2_2") (pintype "passive"))
      (node (ref "C61") (pin "2") (pinfunction "2_2") (pintype "passive"))
      (node (ref "R150") (pin "1") (pinfunction "1_1") (pintype "passive"))
      (node (ref "R151") (pin "2") (pinfunction "2_2") (pintype "passive"))
      (node (ref "R152") (pin "1") (pinfunction "1_1") (pintype "passive"))
      (node (ref "R157") (pin "1") (pinfunction "1_1") (pintype "passive"))
      (node (ref "U14") (pin "25") (pinfunction "EP_25") (pintype "passive"))
      (node (ref "U15") (pin "13") (pinfunction "GND_13") (pintype "power_in"))
      (node (ref "U15") (pin "21") (pinfunction "GND_21") (pintype "power_in"))
      (node (ref "U15") (pin "3") (pinfunction "GND_3") (pintype "power_in"))
      (node (ref "X3") (pin "2") (pintype "passive"))
      (node (ref "X3") (pin "4") (pintype "passive"))
    )
    (net (code "54") (name "Net-(U14-CRFILT)") (class "Default")
      (node (ref "C57") (pin "1") (pinfunction "1_1") (pintype "passive"))
      (node (ref "U14") (pin "10") (pinfunction "CRFILT_10") (pintype "passive"))
    )
    (net (code "55") (name "Net-(U14-RBIAS)") (class "Default")
      (node (ref "R157") (pin "2") (pinfunction "2_2") (pintype "passive"))
      (node (ref "U14") (pin "24") (pinfunction "RBIAS_24") (pintype "passive"))
    )
    (net (code "56") (name "Net-(U14-RESET_N)") (class "Default")
      (node (ref "R147") (pin "1") (pinfunction "1_1") (pintype "passive"))
      (node (ref "U14") (pin "15") (pinfunction "RESET_N_15") (pintype "passive"))
    )
    (net (code "57") (name "Net-(U14-SMBCLK{slash}CFG_SEL0)") (class "Default")
      (node (ref "R151") (pin "1") (pinfunction "1_1") (pintype "passive"))
      (node (ref "U14") (pin "14") (pinfunction "SMBCLK/CFG_SEL0_14") (pintype "passive"))
    )
    (net (code "58") (name "Net-(U14-SMBDATA{slash}NON_REM1)") (class "Default")
      (node (ref "R149") (pin "1") (pinfunction "1_1") (pintype "passive"))
      (node (ref "U14") (pin "13") (pinfunction "SMBDATA/NON_REM1_13") (pintype "passive"))
    )
    (net (code "59") (name "Net-(U14-SUSP_IND{slash}LOCAL_PWR{slash}(NON_REM0))") (class "Default")
      (node (ref "R152") (pin "2") (pinfunction "2_2") (pintype "passive"))
      (node (ref "U14") (pin "17") (pinfunction "SUSP_IND/LOCAL_PWR/(NON_REM0)_17") (pintype "passive"))
    )
    (net (code "60") (name "Net-(U14-VBUS_DET)") (class "Default")
      (node (ref "R148") (pin "1") (pinfunction "1_1") (pintype "passive"))
      (node (ref "R150") (pin "2") (pinfunction "2_2") (pintype "passive"))
      (node (ref "U14") (pin "16") (pinfunction "VBUS_DET_16") (pintype "passive"))
    )
    (net (code "61") (name "Net-(U14-XTALIN{slash}CLKIN)") (class "Default")
      (node (ref "C59") (pin "1") (pinfunction "1_1") (pintype "passive"))
      (node (ref "U14") (pin "22") (pinfunction "XTALIN/CLKIN_22") (pintype "passive"))
      (node (ref "X3") (pin "3") (pintype "passive"))
    )
    (net (code "62") (name "Net-(U14-XTALOUT{slash}(CLKIN_EN))") (class "Default")
      (node (ref "C58") (pin "1") (pinfunction "1_1") (pintype "passive"))
      (node (ref "U14") (pin "21") (pinfunction "XTALOUT/(CLKIN_EN)_21") (pintype "passive"))
      (node (ref "X3") (pin "1") (pintype "passive"))
    )
    (net (code "63") (name "Net-(U15-3V3OUT)") (class "Default")
      (node (ref "C53") (pin "1") (pinfunction "1_1") (pintype "passive"))
      (node (ref "C54") (pin "1") (pinfunction "1_1") (pintype "passive"))
      (node (ref "C55") (pin "1") (pinfunction "1_1") (pintype "passive"))
      (node (ref "C60") (pin "1") (pinfunction "1_1") (pintype "passive"))
      (node (ref "F2") (pin "2") (pinfunction "2_2") (pintype "passive"))
      (node (ref "R156") (pin "1") (pinfunction "1_1") (pintype "passive"))
      (node (ref "U15") (pin "10") (pinfunction "3V3OUT_10") (pintype "input"))
      (node (ref "U15") (pin "11") (pinfunction "~{RESET}_11") (pintype "input"))
      (node (ref "U15") (pin "12") (pinfunction "VCC_12") (pintype "power_in"))
    )
    (net (code "64") (name "Net-(U15-CBUS0)") (class "Default")
      (node (ref "R217") (pin "2") (pinfunction "2_2") (pintype "passive"))
      (node (ref "U15") (pin "15") (pinfunction "CBUS0_15") (pintype "bidirectional"))
    )
    (net (code "65") (name "Net-(U15-CBUS1)") (class "Default")
      (node (ref "R158") (pin "1") (pinfunction "1_1") (pintype "passive"))
      (node (ref "U15") (pin "14") (pinfunction "CBUS1_14") (pintype "bidirectional"))
    )
    (net (code "66") (name "Net-(U15-CBUS3)") (class "Default")
      (node (ref "R159") (pin "1") (pinfunction "1_1") (pintype "passive"))
      (node (ref "U15") (pin "16") (pinfunction "CBUS3_16") (pintype "bidirectional"))
    )
    (net (code "67") (name "Net-(U15-VCCIO)") (class "Default")
      (node (ref "R155") (pin "2") (pinfunction "2_2") (pintype "passive"))
      (node (ref "R156") (pin "2") (pinfunction "2_2") (pintype "passive"))
      (node (ref "U15") (pin "20") (pinfunction "VCCIO_20") (pintype "power_in"))
    )
    (net (code "68") (name "VDDIO_Periph") (class "Default")
      (node (ref "R155") (pin "1") (pinfunction "1_1") (pintype "passive"))
      (node (ref "TP28") (pin "1") (pintype "passive"))
    )
    (net (code "69") (name "unconnected-(U14-NC-Pad6)") (class "Default")
      (node (ref "U14") (pin "6") (pinfunction "NC_6") (pintype "passive+no_connect"))
    )
    (net (code "70") (name "unconnected-(U14-OCS1_N-Pad8)") (class "Default")
      (node (ref "U14") (pin "8") (pinfunction "OCS1_N_8") (pintype "passive+no_connect"))
    )
    (net (code "71") (name "unconnected-(U14-OCS2_N-Pad12)") (class "Default")
      (node (ref "U14") (pin "12") (pinfunction "OCS2_N_12") (pintype "passive+no_connect"))
    )
    (net (code "72") (name "unconnected-(U14-PLLFILT-Pad23)") (class "Default")
      (node (ref "U14") (pin "23") (pinfunction "PLLFILT_23") (pintype "passive+no_connect"))
    )
    (net (code "73") (name "unconnected-(U14-PRTPWR1{slash}(BC_EN1)-Pad7)") (class "Default")
      (node (ref "U14") (pin "7") (pinfunction "PRTPWR1/(BC_EN1)_7") (pintype "passive+no_connect"))
    )
    (net (code "74") (name "unconnected-(U14-PRTPWR2-Pad11)") (class "Default")
      (node (ref "U14") (pin "11") (pinfunction "PRTPWR2_11") (pintype "passive+no_connect"))
    )
    (net (code "75") (name "unconnected-(U15-CBUS2-Pad7)") (class "Default")
      (node (ref "U15") (pin "7") (pinfunction "CBUS2_7") (pintype "bidirectional+no_connect"))
    )
    (net (code "76") (name "unconnected-(U15-~{DCD}-Pad5)") (class "Default")
      (node (ref "U15") (pin "5") (pinfunction "~{DCD}_5") (pintype "input+no_connect"))
    )
    (net (code "77") (name "unconnected-(U15-~{RI}-Pad2)") (class "Default")
      (node (ref "U15") (pin "2") (pinfunction "~{RI}_2") (pintype "input+no_connect"))
    )
  )
)
